# snare_host_brd.net
KiCad netlist of a schematic drawn in EAGLE
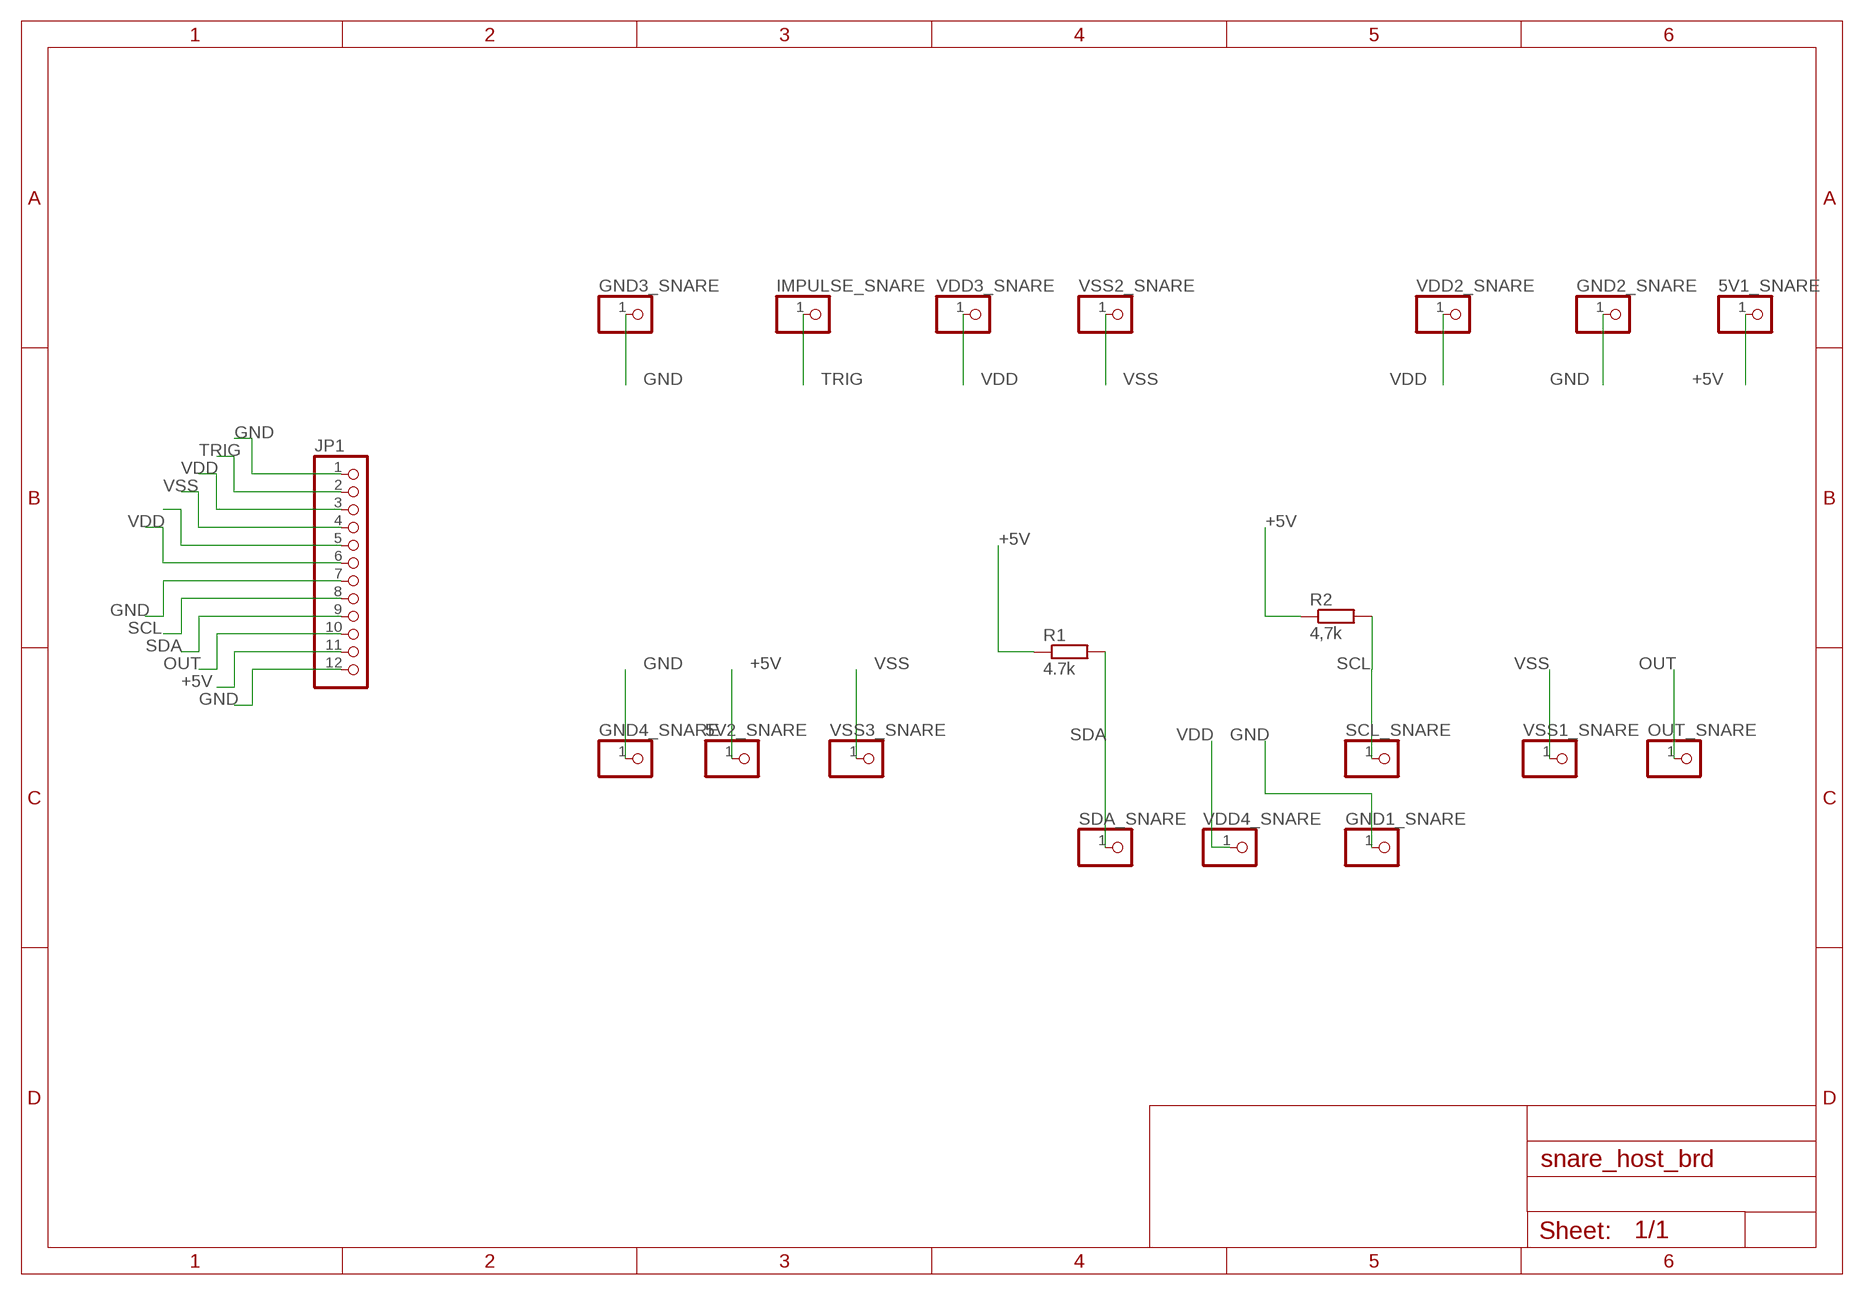
[diagram p0: schematic, sheet 1]

(export (version "E")
  (design (tool "Eeschema 10.0.6"))
  (components
    (comp (ref "5V1_SNARE")
      (value "PINHD-1X1")
      (footprint "eagle-import:1X01")
      (libsource (lib "eagle-import") (part "PINHD-1X1"))
    )
    (comp (ref "5V2_SNARE")
      (value "PINHD-1X1")
      (footprint "eagle-import:1X01")
      (libsource (lib "eagle-import") (part "PINHD-1X1"))
    )
    (comp (ref "GND1_SNARE")
      (value "PINHD-1X1")
      (footprint "eagle-import:1X01")
      (libsource (lib "eagle-import") (part "PINHD-1X1"))
    )
    (comp (ref "GND2_SNARE")
      (value "PINHD-1X1")
      (footprint "eagle-import:1X01")
      (libsource (lib "eagle-import") (part "PINHD-1X1"))
    )
    (comp (ref "GND3_SNARE")
      (value "PINHD-1X1")
      (footprint "eagle-import:1X01")
      (libsource (lib "eagle-import") (part "PINHD-1X1"))
    )
    (comp (ref "GND4_SNARE")
      (value "PINHD-1X1")
      (footprint "eagle-import:1X01")
      (libsource (lib "eagle-import") (part "PINHD-1X1"))
    )
    (comp (ref "IMPULSE_SNARE")
      (value "PINHD-1X1")
      (footprint "eagle-import:1X01")
      (libsource (lib "eagle-import") (part "PINHD-1X1"))
    )
    (comp (ref "JP1")
      (value "PINHD-1X12/90")
      (footprint "eagle-import:1X12_90")
      (libsource (lib "eagle-import") (part "PINHD-1X12/90"))
    )
    (comp (ref "OUT_SNARE")
      (value "PINHD-1X1")
      (footprint "eagle-import:1X01")
      (libsource (lib "eagle-import") (part "PINHD-1X1"))
    )
    (comp (ref "R1")
      (value "4.7k")
      (footprint "eagle-import:0207_10")
      (libsource (lib "eagle-import") (part "R-EU_0207/10"))
    )
    (comp (ref "R2")
      (value "4,7k")
      (footprint "eagle-import:0207_10")
      (libsource (lib "eagle-import") (part "R-EU_0207/10"))
    )
    (comp (ref "SCL_SNARE")
      (value "PINHD-1X1")
      (footprint "eagle-import:1X01")
      (libsource (lib "eagle-import") (part "PINHD-1X1"))
    )
    (comp (ref "SDA_SNARE")
      (value "PINHD-1X1")
      (footprint "eagle-import:1X01")
      (libsource (lib "eagle-import") (part "PINHD-1X1"))
    )
    (comp (ref "VDD2_SNARE")
      (value "PINHD-1X1")
      (footprint "eagle-import:1X01")
      (libsource (lib "eagle-import") (part "PINHD-1X1"))
    )
    (comp (ref "VDD3_SNARE")
      (value "PINHD-1X1")
      (footprint "eagle-import:1X01")
      (libsource (lib "eagle-import") (part "PINHD-1X1"))
    )
    (comp (ref "VDD4_SNARE")
      (value "PINHD-1X1")
      (footprint "eagle-import:1X01")
      (libsource (lib "eagle-import") (part "PINHD-1X1"))
    )
    (comp (ref "VSS1_SNARE")
      (value "PINHD-1X1")
      (footprint "eagle-import:1X01")
      (libsource (lib "eagle-import") (part "PINHD-1X1"))
    )
    (comp (ref "VSS2_SNARE")
      (value "PINHD-1X1")
      (footprint "eagle-import:1X01")
      (libsource (lib "eagle-import") (part "PINHD-1X1"))
    )
    (comp (ref "VSS3_SNARE")
      (value "PINHD-1X1")
      (footprint "eagle-import:1X01")
      (libsource (lib "eagle-import") (part "PINHD-1X1"))
    )
  )
  (nets
    (net (code "1") (name "/+5V") (class "Default")
      (node (ref "5V1_SNARE") (pin "1") (pinfunction "1_1") (pintype "passive"))
      (node (ref "5V2_SNARE") (pin "1") (pinfunction "1_1") (pintype "passive"))
      (node (ref "JP1") (pin "11") (pinfunction "11_11") (pintype "passive"))
      (node (ref "R1") (pin "1") (pinfunction "1_1") (pintype "passive"))
      (node (ref "R2") (pin "1") (pinfunction "1_1") (pintype "passive"))
    )
    (net (code "2") (name "/GND") (class "Default")
      (node (ref "GND1_SNARE") (pin "1") (pinfunction "1_1") (pintype "passive"))
      (node (ref "GND2_SNARE") (pin "1") (pinfunction "1_1") (pintype "passive"))
      (node (ref "GND3_SNARE") (pin "1") (pinfunction "1_1") (pintype "passive"))
      (node (ref "GND4_SNARE") (pin "1") (pinfunction "1_1") (pintype "passive"))
      (node (ref "JP1") (pin "1") (pinfunction "1_1") (pintype "passive"))
      (node (ref "JP1") (pin "12") (pinfunction "12_12") (pintype "passive"))
      (node (ref "JP1") (pin "7") (pinfunction "7_7") (pintype "passive"))
    )
    (net (code "3") (name "/OUT") (class "Default")
      (node (ref "JP1") (pin "10") (pinfunction "10_10") (pintype "passive"))
      (node (ref "OUT_SNARE") (pin "1") (pinfunction "1_1") (pintype "passive"))
    )
    (net (code "4") (name "/SCL") (class "Default")
      (node (ref "JP1") (pin "8") (pinfunction "8_8") (pintype "passive"))
      (node (ref "R2") (pin "2") (pinfunction "2_2") (pintype "passive"))
      (node (ref "SCL_SNARE") (pin "1") (pinfunction "1_1") (pintype "passive"))
    )
    (net (code "5") (name "/SDA") (class "Default")
      (node (ref "JP1") (pin "9") (pinfunction "9_9") (pintype "passive"))
      (node (ref "R1") (pin "2") (pinfunction "2_2") (pintype "passive"))
      (node (ref "SDA_SNARE") (pin "1") (pinfunction "1_1") (pintype "passive"))
    )
    (net (code "6") (name "/TRIG") (class "Default")
      (node (ref "IMPULSE_SNARE") (pin "1") (pinfunction "1_1") (pintype "passive"))
      (node (ref "JP1") (pin "2") (pinfunction "2_2") (pintype "passive"))
    )
    (net (code "7") (name "/VDD") (class "Default")
      (node (ref "JP1") (pin "3") (pinfunction "3_3") (pintype "passive"))
      (node (ref "JP1") (pin "6") (pinfunction "6_6") (pintype "passive"))
      (node (ref "VDD2_SNARE") (pin "1") (pinfunction "1_1") (pintype "passive"))
      (node (ref "VDD3_SNARE") (pin "1") (pinfunction "1_1") (pintype "passive"))
      (node (ref "VDD4_SNARE") (pin "1") (pinfunction "1_1") (pintype "passive"))
    )
    (net (code "8") (name "/VSS") (class "Default")
      (node (ref "JP1") (pin "4") (pinfunction "4_4") (pintype "passive"))
      (node (ref "VSS1_SNARE") (pin "1") (pinfunction "1_1") (pintype "passive"))
      (node (ref "VSS2_SNARE") (pin "1") (pinfunction "1_1") (pintype "passive"))
      (node (ref "VSS3_SNARE") (pin "1") (pinfunction "1_1") (pintype "passive"))
    )
    (net (code "9") (name "unconnected-(JP1-Pad5)") (class "Default")
      (node (ref "JP1") (pin "5") (pinfunction "5_5") (pintype "passive"))
    )
  )
)
